# MB1183.net
KiCad netlist of a schematic drawn in Altium Designer
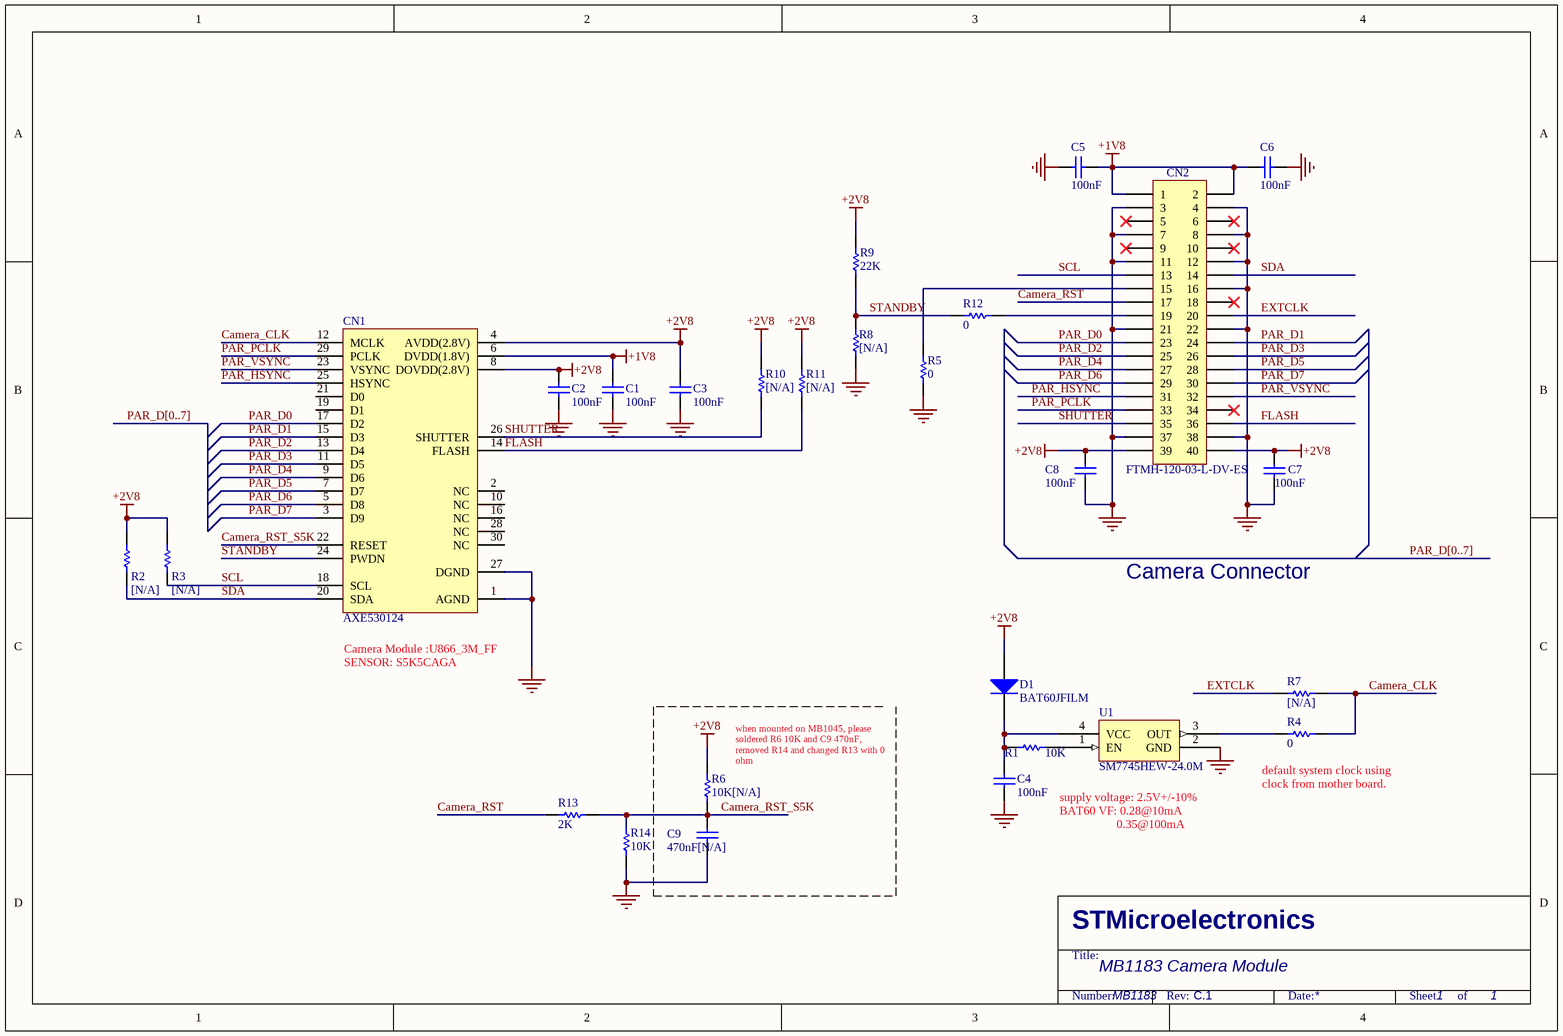
[diagram p0: MB1183.SchDoc]

(export (version "E")
  (design (tool "Eeschema 10.0.6"))
  (components
    (comp (ref "C1")
      (value "100nF")
      (footprint "0603C")
      (description "Capacitor")
      (fields (field (name "PUBLISHER") "Altium Limited"))
      (libsource (lib "Miscellaneous Devices") (part "Cap"))
    )
    (comp (ref "C2")
      (value "100nF")
      (footprint "0603C")
      (description "Capacitor")
      (fields (field (name "PUBLISHER") "Altium Limited"))
      (libsource (lib "Miscellaneous Devices") (part "Cap"))
    )
    (comp (ref "C3")
      (value "100nF")
      (footprint "0603C")
      (description "Capacitor")
      (fields (field (name "PUBLISHER") "Altium Limited"))
      (libsource (lib "Miscellaneous Devices") (part "Cap"))
    )
    (comp (ref "C4")
      (value "100nF")
      (footprint "0603C")
      (description "Capacitor")
      (fields (field (name "PUBLISHER") "Altium Limited"))
      (libsource (lib "Miscellaneous Devices") (part "Cap"))
    )
    (comp (ref "C5")
      (value "100nF")
      (footprint "0603C")
      (description "Capacitor")
      (fields (field (name "PUBLISHER") "Altium Limited"))
      (libsource (lib "Miscellaneous Devices") (part "Cap"))
    )
    (comp (ref "C6")
      (value "100nF")
      (footprint "0603C")
      (description "Capacitor")
      (fields (field (name "PUBLISHER") "Altium Limited"))
      (libsource (lib "Miscellaneous Devices") (part "Cap"))
    )
    (comp (ref "C7")
      (value "100nF")
      (footprint "0603C")
      (description "Capacitor")
      (fields (field (name "PUBLISHER") "Altium Limited"))
      (libsource (lib "Miscellaneous Devices") (part "Cap"))
    )
    (comp (ref "C8")
      (value "100nF")
      (footprint "0603C")
      (description "Capacitor")
      (fields (field (name "PUBLISHER") "Altium Limited"))
      (libsource (lib "Miscellaneous Devices") (part "Cap"))
    )
    (comp (ref "C9")
      (value "470nF[N/A]")
      (footprint "0603C")
      (description "Capacitor")
      (fields (field (name "PUBLISHER") "Altium Limited"))
      (libsource (lib "Miscellaneous Devices") (part "Cap"))
    )
    (comp (ref "CN1")
      (value "AXE530124")
      (footprint "AXE530124")
      (description "CAMERA MODULE")
      (libsource (lib "MB1183") (part "U866_3M_FF"))
    )
    (comp (ref "CN2")
      (value "FTMH-120-03-L-DV-ES")
      (footprint "FTMH-120-03-L-DV-ES")
      (description "20*2Pins, 1mm_SMT, male")
      (fields (field (name "PUBLISHER") "Altium Limited"))
      (libsource (lib "Miscellaneous Connectors") (part "Header 20X2"))
    )
    (comp (ref "D1")
      (value "BAT60JFILM")
      (footprint "SOD-323")
      (description "Default Diode")
      (fields (field (name "PUBLISHER") "Altium Limited"))
      (libsource (lib "Miscellaneous Devices") (part "Diode"))
    )
    (comp (ref "R1")
      (value "10K")
      (footprint "0603R")
      (description "Resistor")
      (fields (field (name "PUBLISHER") "Altium Limited"))
      (libsource (lib "Miscellaneous Devices") (part "Res1"))
    )
    (comp (ref "R2")
      (value "[N/A]")
      (footprint "0603R")
      (description "Resistor 10K")
      (fields (field (name "PUBLISHER") "Altium Limited"))
      (libsource (lib "Miscellaneous Devices") (part "Res1"))
    )
    (comp (ref "R3")
      (value "[N/A]")
      (footprint "0603R")
      (description "Resistor")
      (fields (field (name "PUBLISHER") "Altium Limited"))
      (libsource (lib "Miscellaneous Devices") (part "Res1"))
    )
    (comp (ref "R4")
      (value "0")
      (footprint "0603R")
      (description "Resistor")
      (fields (field (name "PUBLISHER") "Altium Limited"))
      (libsource (lib "Miscellaneous Devices") (part "Res1"))
    )
    (comp (ref "R5")
      (value "0")
      (footprint "0603R")
      (description "Resistor")
      (fields (field (name "PUBLISHER") "Altium Limited"))
      (libsource (lib "Miscellaneous Devices") (part "Res1"))
    )
    (comp (ref "R6")
      (value "10K[N/A]")
      (footprint "0603R")
      (description "Resistor")
      (fields (field (name "PUBLISHER") "Altium Limited"))
      (libsource (lib "Miscellaneous Devices") (part "Res1"))
    )
    (comp (ref "R7")
      (value "[N/A]")
      (footprint "0603R")
      (description "Resistor")
      (fields (field (name "PUBLISHER") "Altium Limited"))
      (libsource (lib "Miscellaneous Devices") (part "Res1"))
    )
    (comp (ref "R8")
      (value "[N/A]")
      (footprint "0603R")
      (description "Resistor")
      (fields (field (name "PUBLISHER") "Altium Limited"))
      (libsource (lib "Miscellaneous Devices") (part "Res1"))
    )
    (comp (ref "R9")
      (value "22K")
      (footprint "0603R")
      (description "Resistor")
      (fields (field (name "PUBLISHER") "Altium Limited"))
      (libsource (lib "Miscellaneous Devices") (part "Res1"))
    )
    (comp (ref "R10")
      (value "[N/A]")
      (footprint "0603R")
      (description "Resistor")
      (fields (field (name "PUBLISHER") "Altium Limited"))
      (libsource (lib "Miscellaneous Devices") (part "Res1"))
    )
    (comp (ref "R11")
      (value "[N/A]")
      (footprint "0603R")
      (description "Resistor")
      (fields (field (name "PUBLISHER") "Altium Limited"))
      (libsource (lib "Miscellaneous Devices") (part "Res1"))
    )
    (comp (ref "R12")
      (value "0")
      (footprint "0603R")
      (description "Resistor")
      (fields (field (name "PUBLISHER") "Altium Limited"))
      (libsource (lib "Miscellaneous Devices") (part "Res1"))
    )
    (comp (ref "R13")
      (value "2K")
      (footprint "0603R")
      (description "Resistor")
      (fields (field (name "PUBLISHER") "Altium Limited"))
      (libsource (lib "Miscellaneous Devices") (part "Res1"))
    )
    (comp (ref "R14")
      (value "10K")
      (footprint "0603R")
      (description "Resistor")
      (fields (field (name "PUBLISHER") "Altium Limited"))
      (libsource (lib "Miscellaneous Devices") (part "Res1"))
    )
    (comp (ref "U1")
      (value "SM7745HEW-24.0M")
      (footprint "XTAL_5X7")
      (libsource (lib "MB784") (part "SM7745HEV-50.0M"))
    )
  )
  (nets
    (net (code "1") (name "+1V8") (class "Default")
      (node (ref "C1") (pin "1") (pinfunction "1_1") (pintype "passive"))
      (node (ref "C5") (pin "2") (pinfunction "2_2") (pintype "passive"))
      (node (ref "C6") (pin "1") (pinfunction "1_1") (pintype "passive"))
      (node (ref "CN1") (pin "6") (pinfunction "DVDD(1.8V)_6") (pintype "passive"))
      (node (ref "CN2") (pin "1") (pinfunction "1_1") (pintype "passive"))
      (node (ref "CN2") (pin "2") (pinfunction "2_2") (pintype "passive"))
    )
    (net (code "2") (name "+2V8") (class "Default")
      (node (ref "C2") (pin "1") (pinfunction "1_1") (pintype "passive"))
      (node (ref "C3") (pin "1") (pinfunction "1_1") (pintype "passive"))
      (node (ref "C7") (pin "1") (pinfunction "1_1") (pintype "passive"))
      (node (ref "C8") (pin "1") (pinfunction "1_1") (pintype "passive"))
      (node (ref "CN1") (pin "4") (pinfunction "AVDD(2.8V)_4") (pintype "passive"))
      (node (ref "CN1") (pin "8") (pinfunction "DOVDD(2.8V)_8") (pintype "passive"))
      (node (ref "CN2") (pin "39") (pinfunction "39_39") (pintype "passive"))
      (node (ref "CN2") (pin "40") (pinfunction "40_40") (pintype "passive"))
      (node (ref "D1") (pin "1") (pinfunction "A_1") (pintype "passive"))
      (node (ref "R10") (pin "1") (pinfunction "1_1") (pintype "passive"))
      (node (ref "R11") (pin "1") (pinfunction "1_1") (pintype "passive"))
      (node (ref "R2") (pin "1") (pinfunction "1_1") (pintype "passive"))
      (node (ref "R3") (pin "1") (pinfunction "1_1") (pintype "passive"))
      (node (ref "R6") (pin "1") (pinfunction "1_1") (pintype "passive"))
      (node (ref "R9") (pin "1") (pinfunction "1_1") (pintype "passive"))
    )
    (net (code "3") (name "/Camera_CLK") (class "Default")
      (node (ref "CN1") (pin "12") (pinfunction "MCLK_12") (pintype "passive"))
      (node (ref "R4") (pin "2") (pinfunction "2_2") (pintype "passive"))
      (node (ref "R7") (pin "2") (pinfunction "2_2") (pintype "passive"))
    )
    (net (code "4") (name "/Camera_RST") (class "Default")
      (node (ref "CN2") (pin "17") (pinfunction "17_17") (pintype "passive"))
      (node (ref "R13") (pin "1") (pinfunction "1_1") (pintype "passive"))
    )
    (net (code "5") (name "/Camera_RST_S5K") (class "Default")
      (node (ref "C9") (pin "1") (pinfunction "1_1") (pintype "passive"))
      (node (ref "CN1") (pin "22") (pinfunction "RESET_22") (pintype "passive"))
      (node (ref "R13") (pin "2") (pinfunction "2_2") (pintype "passive"))
      (node (ref "R14") (pin "1") (pinfunction "1_1") (pintype "passive"))
      (node (ref "R6") (pin "2") (pinfunction "2_2") (pintype "passive"))
    )
    (net (code "6") (name "/EXTCLK") (class "Default")
      (node (ref "CN2") (pin "20") (pinfunction "20_20") (pintype "passive"))
      (node (ref "R7") (pin "1") (pinfunction "1_1") (pintype "passive"))
    )
    (net (code "7") (name "/FLASH") (class "Default")
      (node (ref "CN1") (pin "14") (pinfunction "FLASH_14") (pintype "passive"))
      (node (ref "CN2") (pin "36") (pinfunction "36_36") (pintype "passive"))
      (node (ref "R11") (pin "2") (pinfunction "2_2") (pintype "passive"))
    )
    (net (code "8") (name "/PAR_D0") (class "Default")
      (node (ref "CN1") (pin "17") (pinfunction "D2_17") (pintype "passive"))
      (node (ref "CN2") (pin "23") (pinfunction "23_23") (pintype "passive"))
    )
    (net (code "9") (name "/PAR_D1") (class "Default")
      (node (ref "CN1") (pin "15") (pinfunction "D3_15") (pintype "passive"))
      (node (ref "CN2") (pin "24") (pinfunction "24_24") (pintype "passive"))
    )
    (net (code "10") (name "/PAR_D2") (class "Default")
      (node (ref "CN1") (pin "13") (pinfunction "D4_13") (pintype "passive"))
      (node (ref "CN2") (pin "25") (pinfunction "25_25") (pintype "passive"))
    )
    (net (code "11") (name "/PAR_D3") (class "Default")
      (node (ref "CN1") (pin "11") (pinfunction "D5_11") (pintype "passive"))
      (node (ref "CN2") (pin "26") (pinfunction "26_26") (pintype "passive"))
    )
    (net (code "12") (name "/PAR_D4") (class "Default")
      (node (ref "CN1") (pin "9") (pinfunction "D6_9") (pintype "passive"))
      (node (ref "CN2") (pin "27") (pinfunction "27_27") (pintype "passive"))
    )
    (net (code "13") (name "/PAR_D5") (class "Default")
      (node (ref "CN1") (pin "7") (pinfunction "D7_7") (pintype "passive"))
      (node (ref "CN2") (pin "28") (pinfunction "28_28") (pintype "passive"))
    )
    (net (code "14") (name "/PAR_D6") (class "Default")
      (node (ref "CN1") (pin "5") (pinfunction "D8_5") (pintype "passive"))
      (node (ref "CN2") (pin "29") (pinfunction "29_29") (pintype "passive"))
    )
    (net (code "15") (name "/PAR_D7") (class "Default")
      (node (ref "CN1") (pin "3") (pinfunction "D9_3") (pintype "passive"))
      (node (ref "CN2") (pin "30") (pinfunction "30_30") (pintype "passive"))
    )
    (net (code "17") (name "/PAR_HSYNC") (class "Default")
      (node (ref "CN1") (pin "25") (pinfunction "HSYNC_25") (pintype "passive"))
      (node (ref "CN2") (pin "31") (pinfunction "31_31") (pintype "passive"))
    )
    (net (code "18") (name "/PAR_PCLK") (class "Default")
      (node (ref "CN1") (pin "29") (pinfunction "PCLK_29") (pintype "passive"))
      (node (ref "CN2") (pin "33") (pinfunction "33_33") (pintype "passive"))
    )
    (net (code "19") (name "/PAR_VSYNC") (class "Default")
      (node (ref "CN1") (pin "23") (pinfunction "VSYNC_23") (pintype "passive"))
      (node (ref "CN2") (pin "32") (pinfunction "32_32") (pintype "passive"))
    )
    (net (code "20") (name "/SCL") (class "Default")
      (node (ref "CN1") (pin "18") (pinfunction "SCL_18") (pintype "passive"))
      (node (ref "CN2") (pin "13") (pinfunction "13_13") (pintype "passive"))
      (node (ref "R3") (pin "2") (pinfunction "2_2") (pintype "passive"))
    )
    (net (code "21") (name "/SDA") (class "Default")
      (node (ref "CN1") (pin "20") (pinfunction "SDA_20") (pintype "passive"))
      (node (ref "CN2") (pin "14") (pinfunction "14_14") (pintype "passive"))
      (node (ref "R2") (pin "2") (pinfunction "2_2") (pintype "passive"))
    )
    (net (code "22") (name "/SHUTTER") (class "Default")
      (node (ref "CN1") (pin "26") (pinfunction "SHUTTER_26") (pintype "passive"))
      (node (ref "CN2") (pin "35") (pinfunction "35_35") (pintype "passive"))
      (node (ref "R10") (pin "2") (pinfunction "2_2") (pintype "passive"))
    )
    (net (code "23") (name "/STANDBY") (class "Default")
      (node (ref "CN1") (pin "24") (pinfunction "PWDN_24") (pintype "passive"))
      (node (ref "R12") (pin "1") (pinfunction "1_1") (pintype "passive"))
      (node (ref "R8") (pin "2") (pinfunction "2_2") (pintype "passive"))
      (node (ref "R9") (pin "2") (pinfunction "2_2") (pintype "passive"))
    )
    (net (code "24") (name "GND") (class "Default")
      (node (ref "C1") (pin "2") (pinfunction "2_2") (pintype "passive"))
      (node (ref "C2") (pin "2") (pinfunction "2_2") (pintype "passive"))
      (node (ref "C3") (pin "2") (pinfunction "2_2") (pintype "passive"))
      (node (ref "C4") (pin "2") (pinfunction "2_2") (pintype "passive"))
      (node (ref "C5") (pin "1") (pinfunction "1_1") (pintype "passive"))
      (node (ref "C6") (pin "2") (pinfunction "2_2") (pintype "passive"))
      (node (ref "C7") (pin "2") (pinfunction "2_2") (pintype "passive"))
      (node (ref "C8") (pin "2") (pinfunction "2_2") (pintype "passive"))
      (node (ref "C9") (pin "2") (pinfunction "2_2") (pintype "passive"))
      (node (ref "CN1") (pin "1") (pinfunction "AGND_1") (pintype "passive"))
      (node (ref "CN1") (pin "27") (pinfunction "DGND_27") (pintype "passive"))
      (node (ref "CN2") (pin "11") (pinfunction "11_11") (pintype "passive"))
      (node (ref "CN2") (pin "12") (pinfunction "12_12") (pintype "passive"))
      (node (ref "CN2") (pin "16") (pinfunction "16_16") (pintype "passive"))
      (node (ref "CN2") (pin "21") (pinfunction "21_21") (pintype "passive"))
      (node (ref "CN2") (pin "22") (pinfunction "22_22") (pintype "passive"))
      (node (ref "CN2") (pin "3") (pinfunction "3_3") (pintype "passive"))
      (node (ref "CN2") (pin "37") (pinfunction "37_37") (pintype "passive"))
      (node (ref "CN2") (pin "38") (pinfunction "38_38") (pintype "passive"))
      (node (ref "CN2") (pin "4") (pinfunction "4_4") (pintype "passive"))
      (node (ref "CN2") (pin "7") (pinfunction "7_7") (pintype "passive"))
      (node (ref "CN2") (pin "8") (pinfunction "8_8") (pintype "passive"))
      (node (ref "R14") (pin "2") (pinfunction "2_2") (pintype "passive"))
      (node (ref "R5") (pin "2") (pinfunction "2_2") (pintype "passive"))
      (node (ref "R8") (pin "1") (pinfunction "1_1") (pintype "passive"))
      (node (ref "U1") (pin "2") (pinfunction "GND_2") (pintype "passive"))
    )
    (net (code "25") (name "Net-(CN2-Pad15)") (class "Default")
      (node (ref "CN2") (pin "15") (pinfunction "15_15") (pintype "passive"))
      (node (ref "R5") (pin "1") (pinfunction "1_1") (pintype "passive"))
    )
    (net (code "26") (name "Net-(CN2-Pad19)") (class "Default")
      (node (ref "CN2") (pin "19") (pinfunction "19_19") (pintype "passive"))
      (node (ref "R12") (pin "2") (pinfunction "2_2") (pintype "passive"))
    )
    (net (code "27") (name "Net-(D1-K)") (class "Default")
      (node (ref "C4") (pin "1") (pinfunction "1_1") (pintype "passive"))
      (node (ref "D1") (pin "2") (pinfunction "K_2") (pintype "passive"))
      (node (ref "R1") (pin "1") (pinfunction "1_1") (pintype "passive"))
      (node (ref "U1") (pin "4") (pinfunction "VCC_4") (pintype "passive"))
    )
    (net (code "28") (name "Net-(U1-EN)") (class "Default")
      (node (ref "R1") (pin "2") (pinfunction "2_2") (pintype "passive"))
      (node (ref "U1") (pin "1") (pinfunction "EN_1") (pintype "input"))
    )
    (net (code "29") (name "Net-(U1-OUT)") (class "Default")
      (node (ref "R4") (pin "1") (pinfunction "1_1") (pintype "passive"))
      (node (ref "U1") (pin "3") (pinfunction "OUT_3") (pintype "output"))
    )
    (net (code "30") (name "unconnected-(CN1-D0-Pad21)") (class "Default")
      (node (ref "CN1") (pin "21") (pinfunction "D0_21") (pintype "passive"))
    )
    (net (code "31") (name "unconnected-(CN1-D1-Pad19)") (class "Default")
      (node (ref "CN1") (pin "19") (pinfunction "D1_19") (pintype "passive"))
    )
    (net (code "32") (name "unconnected-(CN1-NC-Pad2)") (class "Default")
      (node (ref "CN1") (pin "2") (pinfunction "NC_2") (pintype "passive"))
    )
    (net (code "33") (name "unconnected-(CN1-NC-Pad10)") (class "Default")
      (node (ref "CN1") (pin "10") (pinfunction "NC_10") (pintype "passive"))
    )
    (net (code "34") (name "unconnected-(CN1-NC-Pad16)") (class "Default")
      (node (ref "CN1") (pin "16") (pinfunction "NC_16") (pintype "passive"))
    )
    (net (code "35") (name "unconnected-(CN1-NC-Pad28)") (class "Default")
      (node (ref "CN1") (pin "28") (pinfunction "NC_28") (pintype "passive"))
    )
    (net (code "36") (name "unconnected-(CN1-NC-Pad30)") (class "Default")
      (node (ref "CN1") (pin "30") (pinfunction "NC_30") (pintype "passive"))
    )
    (net (code "37") (name "unconnected-(CN2-Pad5)") (class "Default")
      (node (ref "CN2") (pin "5") (pinfunction "5_5") (pintype "passive+no_connect"))
    )
    (net (code "38") (name "unconnected-(CN2-Pad6)") (class "Default")
      (node (ref "CN2") (pin "6") (pinfunction "6_6") (pintype "passive+no_connect"))
    )
    (net (code "39") (name "unconnected-(CN2-Pad9)") (class "Default")
      (node (ref "CN2") (pin "9") (pinfunction "9_9") (pintype "passive+no_connect"))
    )
    (net (code "40") (name "unconnected-(CN2-Pad10)") (class "Default")
      (node (ref "CN2") (pin "10") (pinfunction "10_10") (pintype "passive+no_connect"))
    )
    (net (code "41") (name "unconnected-(CN2-Pad18)") (class "Default")
      (node (ref "CN2") (pin "18") (pinfunction "18_18") (pintype "passive+no_connect"))
    )
    (net (code "42") (name "unconnected-(CN2-Pad34)") (class "Default")
      (node (ref "CN2") (pin "34") (pinfunction "34_34") (pintype "passive+no_connect"))
    )
  )
)
